# Fake6509_v4.net
KiCad netlist of a schematic drawn in EAGLE
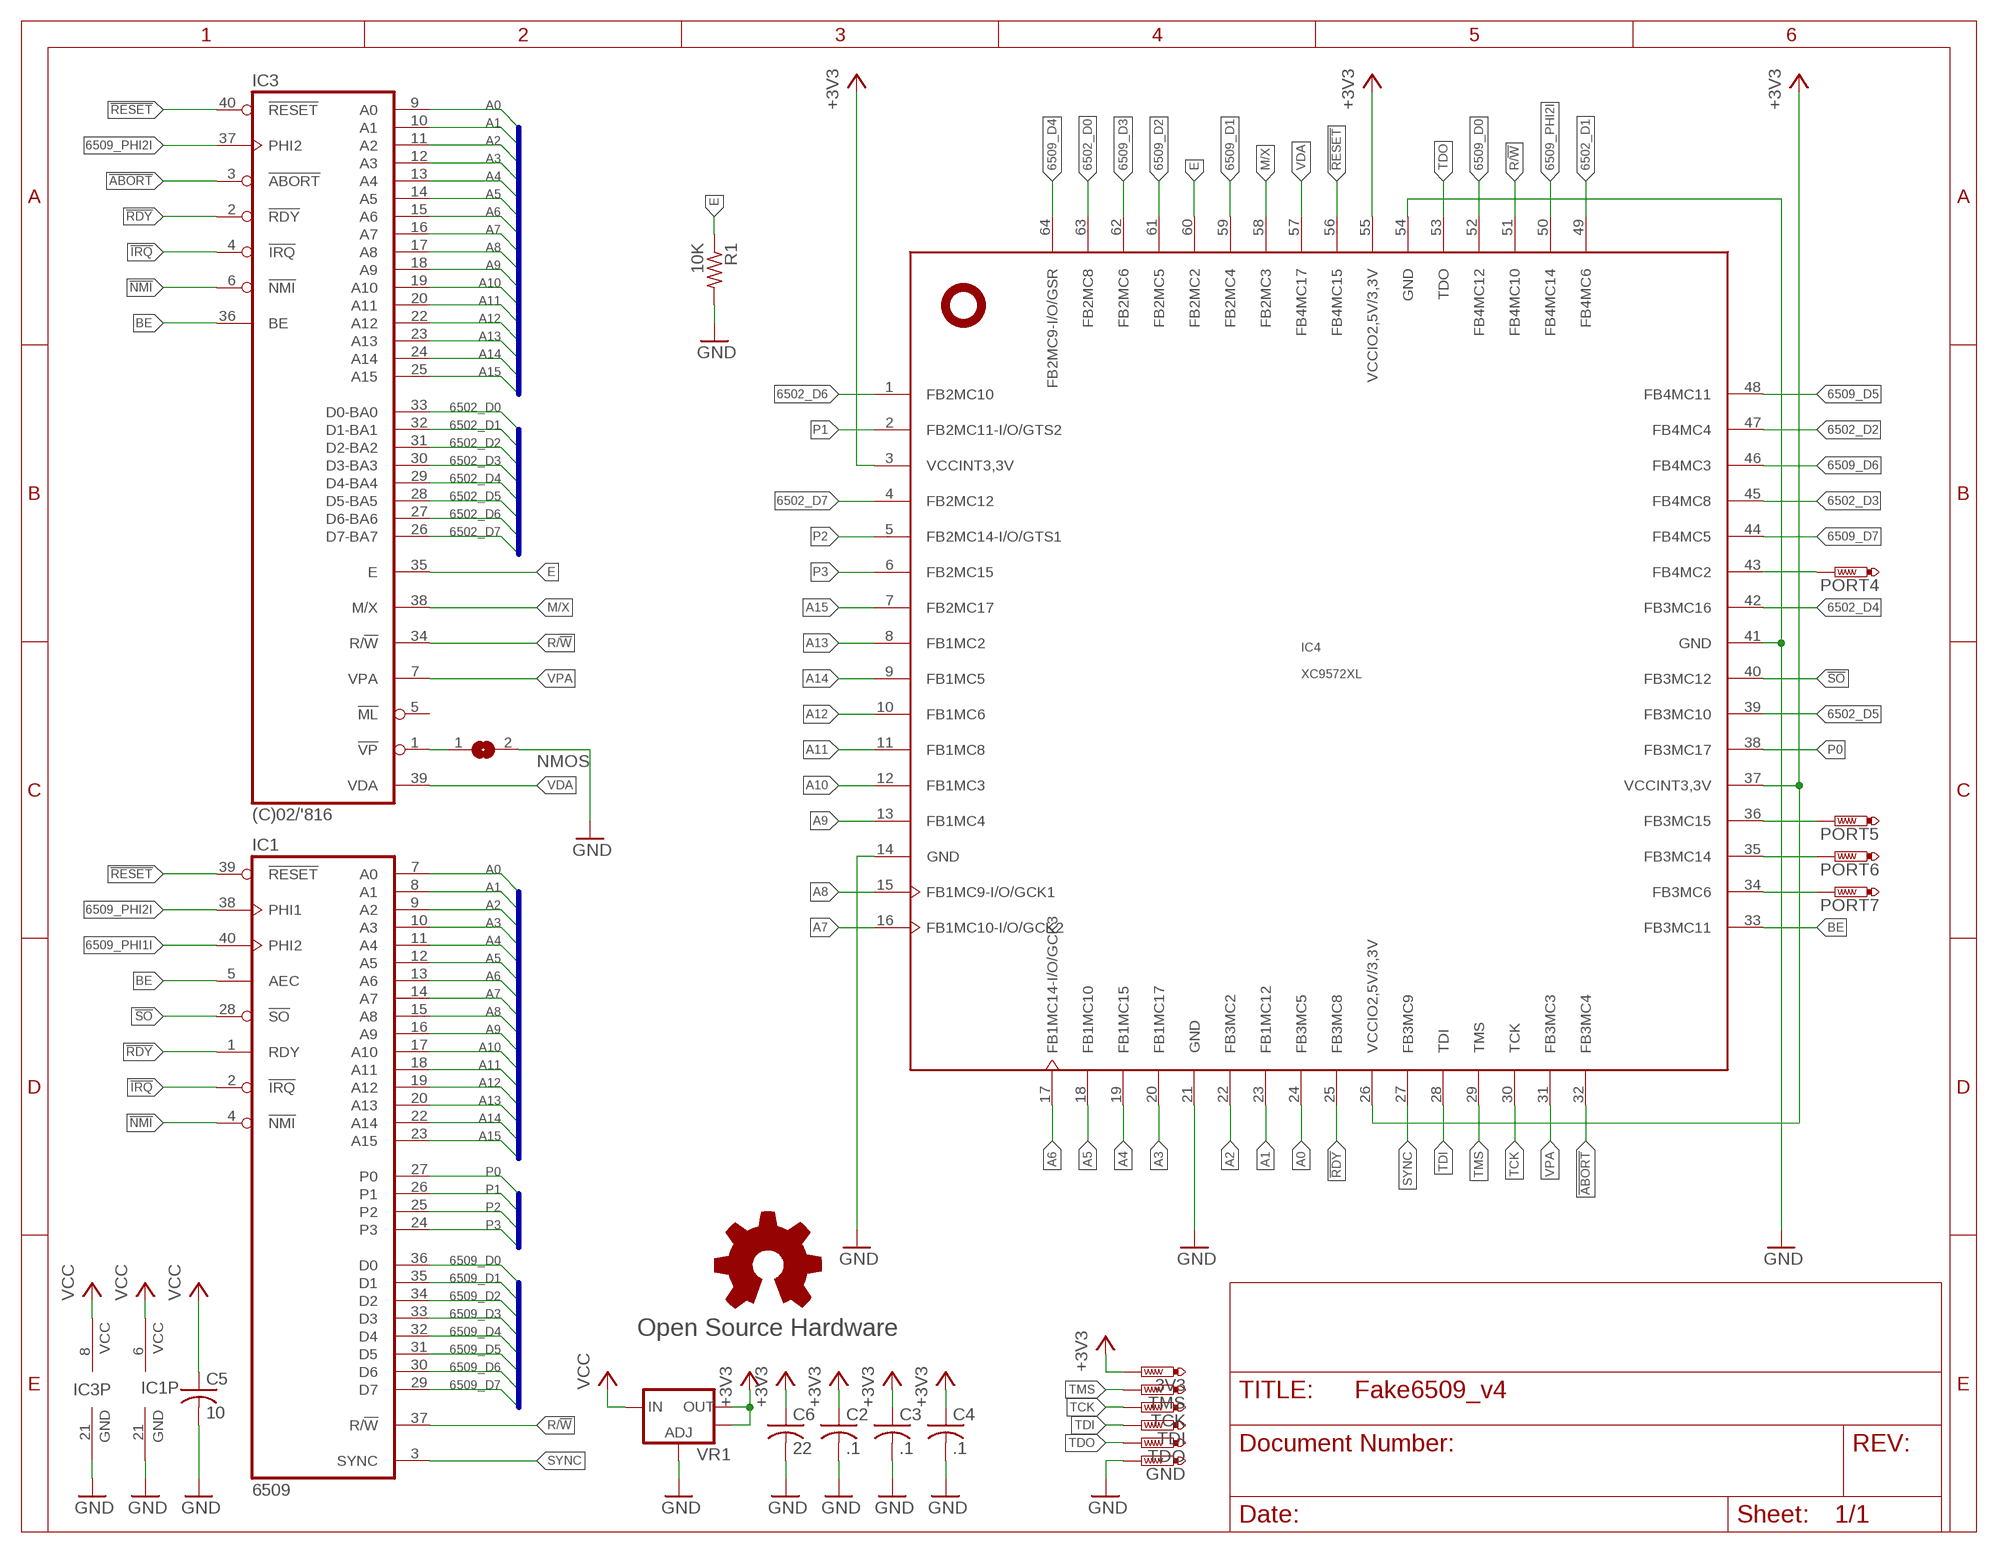
[diagram p0: schematic, sheet 1]

(export (version "E")
  (design (tool "Eeschema 10.0.6"))
  (components
    (comp (ref "3V3")
      (value "PTR1TP08R")
      (footprint "eagle-import:TP08R")
      (libsource (lib "eagle-import") (part "PTR1TP08R"))
    )
    (comp (ref "C2")
      (value ".1")
      (footprint "eagle-import:C0402")
      (libsource (lib "eagle-import") (part "C-USC0402"))
    )
    (comp (ref "C3")
      (value ".1")
      (footprint "eagle-import:C0402")
      (libsource (lib "eagle-import") (part "C-USC0402"))
    )
    (comp (ref "C4")
      (value ".1")
      (footprint "eagle-import:C0402")
      (libsource (lib "eagle-import") (part "C-USC0402"))
    )
    (comp (ref "C5")
      (value "10")
      (footprint "eagle-import:C0805")
      (libsource (lib "eagle-import") (part "C-USC0805"))
    )
    (comp (ref "C6")
      (value "22")
      (footprint "eagle-import:C0805")
      (libsource (lib "eagle-import") (part "C-USC0805"))
    )
    (comp (ref "GND")
      (value "PTR1TP08R")
      (footprint "eagle-import:TP08R")
      (libsource (lib "eagle-import") (part "PTR1TP08R"))
    )
    (comp (ref "GOLD_ORB_SM1")
      (value "Open Source Hardware")
      (footprint "eagle-import:OSHW_5MM")
      (libsource (lib "eagle-import") (part "OSHWLOGOLOGO5MM"))
    )
    (comp (ref "IC1")
      (value "6509")
      (footprint "eagle-import:DIL40-ROUNDPAD")
      (libsource (lib "eagle-import") (part "6509-RP"))
    )
    (comp (ref "IC3")
      (value "(C)02/'816")
      (footprint "eagle-import:DIL40-ROUNDPAD")
      (libsource (lib "eagle-import") (part "W65C816SP-RP"))
    )
    (comp (ref "IC4")
      (value "XC9572XL")
      (footprint "eagle-import:VQFP64")
      (libsource (lib "eagle-import") (part "XC9572XLVQG64"))
    )
    (comp (ref "NMOS")
      (value "SJ")
      (footprint "eagle-import:SJ")
      (libsource (lib "eagle-import") (part "SJ"))
    )
    (comp (ref "PORT4")
      (value "PTR1TP08R")
      (footprint "eagle-import:TP08R")
      (libsource (lib "eagle-import") (part "PTR1TP08R"))
    )
    (comp (ref "PORT5")
      (value "PTR1TP08R")
      (footprint "eagle-import:TP08R")
      (libsource (lib "eagle-import") (part "PTR1TP08R"))
    )
    (comp (ref "PORT6")
      (value "PTR1TP08R")
      (footprint "eagle-import:TP08R")
      (libsource (lib "eagle-import") (part "PTR1TP08R"))
    )
    (comp (ref "PORT7")
      (value "PTR1TP08R")
      (footprint "eagle-import:TP08R")
      (libsource (lib "eagle-import") (part "PTR1TP08R"))
    )
    (comp (ref "R1")
      (value "10K")
      (footprint "eagle-import:R0402")
      (libsource (lib "eagle-import") (part "R-US_R0402"))
    )
    (comp (ref "TCK")
      (value "PTR1TP08R")
      (footprint "eagle-import:TP08R")
      (libsource (lib "eagle-import") (part "PTR1TP08R"))
    )
    (comp (ref "TDI")
      (value "PTR1TP08R")
      (footprint "eagle-import:TP08R")
      (libsource (lib "eagle-import") (part "PTR1TP08R"))
    )
    (comp (ref "TDO")
      (value "PTR1TP08R")
      (footprint "eagle-import:TP08R")
      (libsource (lib "eagle-import") (part "PTR1TP08R"))
    )
    (comp (ref "TMS")
      (value "PTR1TP08R")
      (footprint "eagle-import:TP08R")
      (libsource (lib "eagle-import") (part "PTR1TP08R"))
    )
    (comp (ref "VR1")
      (value "V_REG_LM1117SOT223")
      (footprint "eagle-import:SOT223")
      (libsource (lib "eagle-import") (part "V_REG_LM1117SOT223"))
    )
  )
  (nets
    (net (code "1") (name "+3V3") (class "Default")
      (node (ref "3V3") (pin "TP") (pinfunction "TP_TP") (pintype "input"))
      (node (ref "C2") (pin "1") (pinfunction "1_1") (pintype "passive"))
      (node (ref "C3") (pin "1") (pinfunction "1_1") (pintype "passive"))
      (node (ref "C4") (pin "1") (pinfunction "1_1") (pintype "passive"))
      (node (ref "C6") (pin "1") (pinfunction "1_1") (pintype "passive"))
      (node (ref "IC4") (pin "26") (pinfunction "VCCIO2,5V/3,3V_26") (pintype "power_in"))
      (node (ref "IC4") (pin "3") (pinfunction "VCCINT3,3V_3") (pintype "power_in"))
      (node (ref "IC4") (pin "37") (pinfunction "VCCINT3,3V_37") (pintype "power_in"))
      (node (ref "IC4") (pin "55") (pinfunction "VCCIO2,5V/3,3V_55") (pintype "power_in"))
      (node (ref "VR1") (pin "2") (pinfunction "OUT_2") (pintype "output"))
      (node (ref "VR1") (pin "4") (pinfunction "OUT_4") (pintype "output"))
    )
    (net (code "2") (name "/R{slash}~{W}") (class "Default")
      (node (ref "IC1") (pin "37") (pinfunction "R/~{W}_37") (pintype "output"))
      (node (ref "IC3") (pin "34") (pinfunction "R/~{W}_34") (pintype "output"))
      (node (ref "IC4") (pin "51") (pinfunction "FB4MC10_51") (pintype "bidirectional"))
    )
    (net (code "3") (name "/~{ABORT}") (class "Default")
      (node (ref "IC3") (pin "3") (pinfunction "~{ABORT}_3") (pintype "input"))
      (node (ref "IC4") (pin "32") (pinfunction "FB3MC4_32") (pintype "bidirectional"))
    )
    (net (code "4") (name "/~{IRQ}") (class "Default")
      (node (ref "IC1") (pin "2") (pinfunction "~{IRQ}_2") (pintype "input"))
      (node (ref "IC3") (pin "4") (pinfunction "~{IRQ}_4") (pintype "input"))
    )
    (net (code "5") (name "/~{NMI}") (class "Default")
      (node (ref "IC1") (pin "4") (pinfunction "~{NMI}_4") (pintype "input"))
      (node (ref "IC3") (pin "6") (pinfunction "~{NMI}_6") (pintype "input"))
    )
    (net (code "6") (name "/~{RDY}") (class "Default")
      (node (ref "IC1") (pin "1") (pinfunction "RDY_1") (pintype "input"))
      (node (ref "IC3") (pin "2") (pinfunction "~{RDY}_2") (pintype "bidirectional"))
      (node (ref "IC4") (pin "25") (pinfunction "FB3MC8_25") (pintype "bidirectional"))
    )
    (net (code "7") (name "/~{RESET}") (class "Default")
      (node (ref "IC1") (pin "39") (pinfunction "~{RESET}_39") (pintype "input"))
      (node (ref "IC3") (pin "40") (pinfunction "~{RESET}_40") (pintype "input"))
      (node (ref "IC4") (pin "56") (pinfunction "FB4MC15_56") (pintype "bidirectional"))
    )
    (net (code "8") (name "/~{SO}") (class "Default")
      (node (ref "IC1") (pin "28") (pinfunction "~{SO}_28") (pintype "input"))
      (node (ref "IC4") (pin "40") (pinfunction "FB3MC12_40") (pintype "bidirectional"))
    )
    (net (code "9") (name "6502_D0") (class "Default")
      (node (ref "IC3") (pin "33") (pinfunction "D0-BA0_33") (pintype "bidirectional"))
      (node (ref "IC4") (pin "63") (pinfunction "FB2MC8_63") (pintype "bidirectional"))
    )
    (net (code "10") (name "6502_D1") (class "Default")
      (node (ref "IC3") (pin "32") (pinfunction "D1-BA1_32") (pintype "bidirectional"))
      (node (ref "IC4") (pin "49") (pinfunction "FB4MC6_49") (pintype "bidirectional"))
    )
    (net (code "11") (name "6502_D2") (class "Default")
      (node (ref "IC3") (pin "31") (pinfunction "D2-BA2_31") (pintype "bidirectional"))
      (node (ref "IC4") (pin "47") (pinfunction "FB4MC4_47") (pintype "bidirectional"))
    )
    (net (code "12") (name "6502_D3") (class "Default")
      (node (ref "IC3") (pin "30") (pinfunction "D3-BA3_30") (pintype "bidirectional"))
      (node (ref "IC4") (pin "45") (pinfunction "FB4MC8_45") (pintype "bidirectional"))
    )
    (net (code "13") (name "6502_D4") (class "Default")
      (node (ref "IC3") (pin "29") (pinfunction "D4-BA4_29") (pintype "bidirectional"))
      (node (ref "IC4") (pin "42") (pinfunction "FB3MC16_42") (pintype "bidirectional"))
    )
    (net (code "14") (name "6502_D5") (class "Default")
      (node (ref "IC3") (pin "28") (pinfunction "D5-BA5_28") (pintype "bidirectional"))
      (node (ref "IC4") (pin "39") (pinfunction "FB3MC10_39") (pintype "bidirectional"))
    )
    (net (code "15") (name "6502_D6") (class "Default")
      (node (ref "IC3") (pin "27") (pinfunction "D6-BA6_27") (pintype "bidirectional"))
      (node (ref "IC4") (pin "1") (pinfunction "FB2MC10_1") (pintype "bidirectional"))
    )
    (net (code "16") (name "6502_D7") (class "Default")
      (node (ref "IC3") (pin "26") (pinfunction "D7-BA7_26") (pintype "bidirectional"))
      (node (ref "IC4") (pin "4") (pinfunction "FB2MC12_4") (pintype "bidirectional"))
    )
    (net (code "17") (name "6509_D0") (class "Default")
      (node (ref "IC1") (pin "36") (pinfunction "D0_36") (pintype "bidirectional"))
      (node (ref "IC4") (pin "52") (pinfunction "FB4MC12_52") (pintype "bidirectional"))
    )
    (net (code "18") (name "6509_D1") (class "Default")
      (node (ref "IC1") (pin "35") (pinfunction "D1_35") (pintype "bidirectional"))
      (node (ref "IC4") (pin "59") (pinfunction "FB2MC4_59") (pintype "bidirectional"))
    )
    (net (code "19") (name "6509_D2") (class "Default")
      (node (ref "IC1") (pin "34") (pinfunction "D2_34") (pintype "bidirectional"))
      (node (ref "IC4") (pin "61") (pinfunction "FB2MC5_61") (pintype "bidirectional"))
    )
    (net (code "20") (name "6509_D3") (class "Default")
      (node (ref "IC1") (pin "33") (pinfunction "D3_33") (pintype "bidirectional"))
      (node (ref "IC4") (pin "62") (pinfunction "FB2MC6_62") (pintype "bidirectional"))
    )
    (net (code "21") (name "6509_D4") (class "Default")
      (node (ref "IC1") (pin "32") (pinfunction "D4_32") (pintype "bidirectional"))
      (node (ref "IC4") (pin "64") (pinfunction "FB2MC9-I/O/GSR_64") (pintype "bidirectional"))
    )
    (net (code "22") (name "6509_D5") (class "Default")
      (node (ref "IC1") (pin "31") (pinfunction "D5_31") (pintype "bidirectional"))
      (node (ref "IC4") (pin "48") (pinfunction "FB4MC11_48") (pintype "bidirectional"))
    )
    (net (code "23") (name "6509_D6") (class "Default")
      (node (ref "IC1") (pin "30") (pinfunction "D6_30") (pintype "bidirectional"))
      (node (ref "IC4") (pin "46") (pinfunction "FB4MC3_46") (pintype "bidirectional"))
    )
    (net (code "24") (name "6509_D7") (class "Default")
      (node (ref "IC1") (pin "29") (pinfunction "D7_29") (pintype "bidirectional"))
      (node (ref "IC4") (pin "44") (pinfunction "FB4MC5_44") (pintype "bidirectional"))
    )
    (net (code "25") (name "6509_PHI1I") (class "Default")
      (node (ref "IC1") (pin "40") (pinfunction "PHI2_40") (pintype "input"))
    )
    (net (code "26") (name "6509_PHI2I") (class "Default")
      (node (ref "IC1") (pin "38") (pinfunction "PHI1_38") (pintype "input"))
      (node (ref "IC3") (pin "37") (pinfunction "PHI2_37") (pintype "input"))
      (node (ref "IC4") (pin "50") (pinfunction "FB4MC14_50") (pintype "bidirectional"))
    )
    (net (code "27") (name "A0") (class "Default")
      (node (ref "IC1") (pin "7") (pinfunction "A0_7") (pintype "output"))
      (node (ref "IC3") (pin "9") (pinfunction "A0_9") (pintype "tri_state"))
      (node (ref "IC4") (pin "24") (pinfunction "FB3MC5_24") (pintype "bidirectional"))
    )
    (net (code "28") (name "A1") (class "Default")
      (node (ref "IC1") (pin "8") (pinfunction "A1_8") (pintype "output"))
      (node (ref "IC3") (pin "10") (pinfunction "A1_10") (pintype "tri_state"))
      (node (ref "IC4") (pin "23") (pinfunction "FB1MC12_23") (pintype "bidirectional"))
    )
    (net (code "29") (name "A2") (class "Default")
      (node (ref "IC1") (pin "9") (pinfunction "A2_9") (pintype "output"))
      (node (ref "IC3") (pin "11") (pinfunction "A2_11") (pintype "tri_state"))
      (node (ref "IC4") (pin "22") (pinfunction "FB3MC2_22") (pintype "bidirectional"))
    )
    (net (code "30") (name "A3") (class "Default")
      (node (ref "IC1") (pin "10") (pinfunction "A3_10") (pintype "output"))
      (node (ref "IC3") (pin "12") (pinfunction "A3_12") (pintype "tri_state"))
      (node (ref "IC4") (pin "20") (pinfunction "FB1MC17_20") (pintype "bidirectional"))
    )
    (net (code "31") (name "A4") (class "Default")
      (node (ref "IC1") (pin "11") (pinfunction "A4_11") (pintype "output"))
      (node (ref "IC3") (pin "13") (pinfunction "A4_13") (pintype "tri_state"))
      (node (ref "IC4") (pin "19") (pinfunction "FB1MC15_19") (pintype "bidirectional"))
    )
    (net (code "32") (name "A5") (class "Default")
      (node (ref "IC1") (pin "12") (pinfunction "A5_12") (pintype "output"))
      (node (ref "IC3") (pin "14") (pinfunction "A5_14") (pintype "tri_state"))
      (node (ref "IC4") (pin "18") (pinfunction "FB1MC10_18") (pintype "bidirectional"))
    )
    (net (code "33") (name "A6") (class "Default")
      (node (ref "IC1") (pin "13") (pinfunction "A6_13") (pintype "output"))
      (node (ref "IC3") (pin "15") (pinfunction "A6_15") (pintype "tri_state"))
      (node (ref "IC4") (pin "17") (pinfunction "FB1MC14-I/O/GCK3_17") (pintype "bidirectional"))
    )
    (net (code "34") (name "A7") (class "Default")
      (node (ref "IC1") (pin "14") (pinfunction "A7_14") (pintype "output"))
      (node (ref "IC3") (pin "16") (pinfunction "A7_16") (pintype "tri_state"))
      (node (ref "IC4") (pin "16") (pinfunction "FB1MC10-I/O/GCK2_16") (pintype "bidirectional"))
    )
    (net (code "35") (name "A8") (class "Default")
      (node (ref "IC1") (pin "15") (pinfunction "A8_15") (pintype "output"))
      (node (ref "IC3") (pin "17") (pinfunction "A8_17") (pintype "tri_state"))
      (node (ref "IC4") (pin "15") (pinfunction "FB1MC9-I/O/GCK1_15") (pintype "bidirectional"))
    )
    (net (code "36") (name "A9") (class "Default")
      (node (ref "IC1") (pin "16") (pinfunction "A9_16") (pintype "output"))
      (node (ref "IC3") (pin "18") (pinfunction "A9_18") (pintype "tri_state"))
      (node (ref "IC4") (pin "13") (pinfunction "FB1MC4_13") (pintype "bidirectional"))
    )
    (net (code "37") (name "A10") (class "Default")
      (node (ref "IC1") (pin "17") (pinfunction "A10_17") (pintype "output"))
      (node (ref "IC3") (pin "19") (pinfunction "A10_19") (pintype "tri_state"))
      (node (ref "IC4") (pin "12") (pinfunction "FB1MC3_12") (pintype "bidirectional"))
    )
    (net (code "38") (name "A11") (class "Default")
      (node (ref "IC1") (pin "18") (pinfunction "A11_18") (pintype "output"))
      (node (ref "IC3") (pin "20") (pinfunction "A11_20") (pintype "tri_state"))
      (node (ref "IC4") (pin "11") (pinfunction "FB1MC8_11") (pintype "bidirectional"))
    )
    (net (code "39") (name "A12") (class "Default")
      (node (ref "IC1") (pin "19") (pinfunction "A12_19") (pintype "output"))
      (node (ref "IC3") (pin "22") (pinfunction "A12_22") (pintype "tri_state"))
      (node (ref "IC4") (pin "10") (pinfunction "FB1MC6_10") (pintype "bidirectional"))
    )
    (net (code "40") (name "A13") (class "Default")
      (node (ref "IC1") (pin "20") (pinfunction "A13_20") (pintype "output"))
      (node (ref "IC3") (pin "23") (pinfunction "A13_23") (pintype "tri_state"))
      (node (ref "IC4") (pin "8") (pinfunction "FB1MC2_8") (pintype "bidirectional"))
    )
    (net (code "41") (name "A14") (class "Default")
      (node (ref "IC1") (pin "22") (pinfunction "A14_22") (pintype "output"))
      (node (ref "IC3") (pin "24") (pinfunction "A14_24") (pintype "tri_state"))
      (node (ref "IC4") (pin "9") (pinfunction "FB1MC5_9") (pintype "bidirectional"))
    )
    (net (code "42") (name "A15") (class "Default")
      (node (ref "IC1") (pin "23") (pinfunction "A15_23") (pintype "output"))
      (node (ref "IC3") (pin "25") (pinfunction "A15_25") (pintype "tri_state"))
      (node (ref "IC4") (pin "7") (pinfunction "FB2MC17_7") (pintype "bidirectional"))
    )
    (net (code "43") (name "BE") (class "Default")
      (node (ref "IC1") (pin "5") (pinfunction "AEC_5") (pintype "input"))
      (node (ref "IC3") (pin "36") (pinfunction "BE_36") (pintype "input"))
      (node (ref "IC4") (pin "33") (pinfunction "FB3MC11_33") (pintype "bidirectional"))
    )
    (net (code "44") (name "E") (class "Default")
      (node (ref "IC3") (pin "35") (pinfunction "E_35") (pintype "output"))
      (node (ref "IC4") (pin "60") (pinfunction "FB2MC2_60") (pintype "bidirectional"))
      (node (ref "R1") (pin "1") (pinfunction "1_1") (pintype "passive"))
    )
    (net (code "45") (name "GND") (class "Default")
      (node (ref "C2") (pin "2") (pinfunction "2_2") (pintype "passive"))
      (node (ref "C3") (pin "2") (pinfunction "2_2") (pintype "passive"))
      (node (ref "C4") (pin "2") (pinfunction "2_2") (pintype "passive"))
      (node (ref "C5") (pin "2") (pinfunction "2_2") (pintype "passive"))
      (node (ref "C6") (pin "2") (pinfunction "2_2") (pintype "passive"))
      (node (ref "GND") (pin "TP") (pinfunction "TP_TP") (pintype "input"))
      (node (ref "IC1") (pin "21") (pinfunction "GND_21") (pintype "power_in"))
      (node (ref "IC3") (pin "21") (pinfunction "GND_21") (pintype "power_in"))
      (node (ref "IC4") (pin "14") (pinfunction "GND_14") (pintype "power_in"))
      (node (ref "IC4") (pin "21") (pinfunction "GND_21") (pintype "power_in"))
      (node (ref "IC4") (pin "41") (pinfunction "GND_41") (pintype "power_in"))
      (node (ref "IC4") (pin "54") (pinfunction "GND_54") (pintype "power_in"))
      (node (ref "NMOS") (pin "2") (pinfunction "2_2") (pintype "passive"))
      (node (ref "R1") (pin "2") (pinfunction "2_2") (pintype "passive"))
      (node (ref "VR1") (pin "1") (pinfunction "ADJ_1") (pintype "input"))
    )
    (net (code "46") (name "M{slash}X") (class "Default")
      (node (ref "IC3") (pin "38") (pinfunction "M/X_38") (pintype "output"))
      (node (ref "IC4") (pin "58") (pinfunction "FB2MC3_58") (pintype "bidirectional"))
    )
    (net (code "47") (name "Net-(IC3A-~{VP})") (class "Default")
      (node (ref "IC3") (pin "1") (pinfunction "~{VP}_1") (pintype "output"))
      (node (ref "NMOS") (pin "1") (pinfunction "1_1") (pintype "passive"))
    )
    (net (code "48") (name "Net-(IC4-FB3MC6)") (class "Default")
      (node (ref "IC4") (pin "34") (pinfunction "FB3MC6_34") (pintype "bidirectional"))
      (node (ref "PORT7") (pin "TP") (pinfunction "TP_TP") (pintype "input"))
    )
    (net (code "49") (name "Net-(IC4-FB3MC14)") (class "Default")
      (node (ref "IC4") (pin "35") (pinfunction "FB3MC14_35") (pintype "bidirectional"))
      (node (ref "PORT6") (pin "TP") (pinfunction "TP_TP") (pintype "input"))
    )
    (net (code "50") (name "Net-(IC4-FB3MC15)") (class "Default")
      (node (ref "IC4") (pin "36") (pinfunction "FB3MC15_36") (pintype "bidirectional"))
      (node (ref "PORT5") (pin "TP") (pinfunction "TP_TP") (pintype "input"))
    )
    (net (code "51") (name "Net-(IC4-FB4MC2)") (class "Default")
      (node (ref "IC4") (pin "43") (pinfunction "FB4MC2_43") (pintype "bidirectional"))
      (node (ref "PORT4") (pin "TP") (pinfunction "TP_TP") (pintype "input"))
    )
    (net (code "52") (name "P0") (class "Default")
      (node (ref "IC1") (pin "27") (pinfunction "P0_27") (pintype "output"))
      (node (ref "IC4") (pin "38") (pinfunction "FB3MC17_38") (pintype "bidirectional"))
    )
    (net (code "53") (name "P1") (class "Default")
      (node (ref "IC1") (pin "26") (pinfunction "P1_26") (pintype "output"))
      (node (ref "IC4") (pin "2") (pinfunction "FB2MC11-I/O/GTS2_2") (pintype "bidirectional"))
    )
    (net (code "54") (name "P2") (class "Default")
      (node (ref "IC1") (pin "25") (pinfunction "P2_25") (pintype "output"))
      (node (ref "IC4") (pin "5") (pinfunction "FB2MC14-I/O/GTS1_5") (pintype "bidirectional"))
    )
    (net (code "55") (name "P3") (class "Default")
      (node (ref "IC1") (pin "24") (pinfunction "P3_24") (pintype "output"))
      (node (ref "IC4") (pin "6") (pinfunction "FB2MC15_6") (pintype "bidirectional"))
    )
    (net (code "56") (name "SYNC") (class "Default")
      (node (ref "IC1") (pin "3") (pinfunction "SYNC_3") (pintype "output"))
      (node (ref "IC4") (pin "27") (pinfunction "FB3MC9_27") (pintype "bidirectional"))
    )
    (net (code "57") (name "TCK") (class "Default")
      (node (ref "IC4") (pin "30") (pinfunction "TCK_30") (pintype "bidirectional"))
      (node (ref "TCK") (pin "TP") (pinfunction "TP_TP") (pintype "input"))
    )
    (net (code "58") (name "TDI") (class "Default")
      (node (ref "IC4") (pin "28") (pinfunction "TDI_28") (pintype "bidirectional"))
      (node (ref "TDI") (pin "TP") (pinfunction "TP_TP") (pintype "input"))
    )
    (net (code "59") (name "TDO") (class "Default")
      (node (ref "IC4") (pin "53") (pinfunction "TDO_53") (pintype "bidirectional"))
      (node (ref "TDO") (pin "TP") (pinfunction "TP_TP") (pintype "input"))
    )
    (net (code "60") (name "TMS") (class "Default")
      (node (ref "IC4") (pin "29") (pinfunction "TMS_29") (pintype "bidirectional"))
      (node (ref "TMS") (pin "TP") (pinfunction "TP_TP") (pintype "input"))
    )
    (net (code "61") (name "VCC") (class "Default")
      (node (ref "C5") (pin "1") (pinfunction "1_1") (pintype "passive"))
      (node (ref "IC1") (pin "6") (pinfunction "VCC_6") (pintype "power_in"))
      (node (ref "IC3") (pin "8") (pinfunction "VCC_8") (pintype "power_in"))
      (node (ref "VR1") (pin "3") (pinfunction "IN_3") (pintype "input"))
    )
    (net (code "62") (name "VDA") (class "Default")
      (node (ref "IC3") (pin "39") (pinfunction "VDA_39") (pintype "output"))
      (node (ref "IC4") (pin "57") (pinfunction "FB4MC17_57") (pintype "bidirectional"))
    )
    (net (code "63") (name "VPA") (class "Default")
      (node (ref "IC3") (pin "7") (pinfunction "VPA_7") (pintype "output"))
      (node (ref "IC4") (pin "31") (pinfunction "FB3MC3_31") (pintype "bidirectional"))
    )
    (net (code "64") (name "unconnected-(IC3A-~{ML}-Pad5)") (class "Default")
      (node (ref "IC3") (pin "5") (pinfunction "~{ML}_5") (pintype "output"))
    )
  )
)
